# Saturn.net
KiCad netlist of a schematic drawn in EAGLE
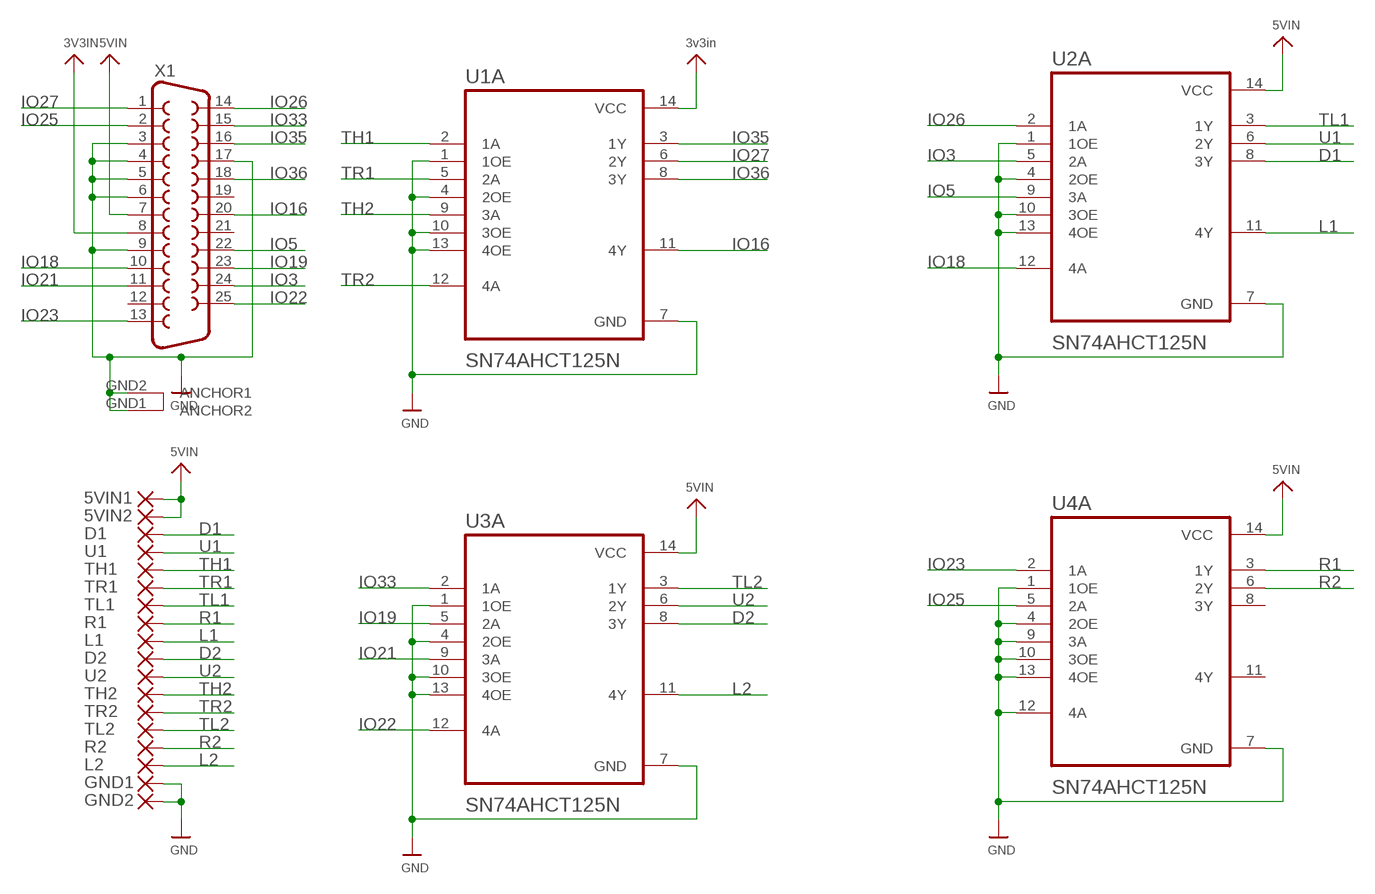
[diagram p0: schematic, sheet 1]

(export (version "E")
  (design (tool "Eeschema 10.0.6"))
  (components
    (comp (ref "5VIN1")
      (value "SMD5")
      (footprint "eagle-import:SMD2,54-5,08")
      (libsource (lib "eagle-import") (part "SMD5"))
    )
    (comp (ref "5VIN2")
      (value "SMD5")
      (footprint "eagle-import:SMD2,54-5,08")
      (libsource (lib "eagle-import") (part "SMD5"))
    )
    (comp (ref "D1")
      (value "SMD5")
      (footprint "eagle-import:SMD2,54-5,08")
      (libsource (lib "eagle-import") (part "SMD5"))
    )
    (comp (ref "D2")
      (value "SMD5")
      (footprint "eagle-import:SMD2,54-5,08")
      (libsource (lib "eagle-import") (part "SMD5"))
    )
    (comp (ref "GND1")
      (value "SMD5")
      (footprint "eagle-import:SMD2,54-5,08")
      (libsource (lib "eagle-import") (part "SMD5"))
    )
    (comp (ref "GND2")
      (value "SMD5")
      (footprint "eagle-import:SMD2,54-5,08")
      (libsource (lib "eagle-import") (part "SMD5"))
    )
    (comp (ref "L1")
      (value "SMD5")
      (footprint "eagle-import:SMD2,54-5,08")
      (libsource (lib "eagle-import") (part "SMD5"))
    )
    (comp (ref "L2")
      (value "SMD5")
      (footprint "eagle-import:SMD2,54-5,08")
      (libsource (lib "eagle-import") (part "SMD5"))
    )
    (comp (ref "R1")
      (value "SMD5")
      (footprint "eagle-import:SMD2,54-5,08")
      (libsource (lib "eagle-import") (part "SMD5"))
    )
    (comp (ref "R2")
      (value "SMD5")
      (footprint "eagle-import:SMD2,54-5,08")
      (libsource (lib "eagle-import") (part "SMD5"))
    )
    (comp (ref "TH1")
      (value "SMD5")
      (footprint "eagle-import:SMD2,54-5,08")
      (libsource (lib "eagle-import") (part "SMD5"))
    )
    (comp (ref "TH2")
      (value "SMD5")
      (footprint "eagle-import:SMD2,54-5,08")
      (libsource (lib "eagle-import") (part "SMD5"))
    )
    (comp (ref "TL1")
      (value "SMD5")
      (footprint "eagle-import:SMD2,54-5,08")
      (libsource (lib "eagle-import") (part "SMD5"))
    )
    (comp (ref "TL2")
      (value "SMD5")
      (footprint "eagle-import:SMD2,54-5,08")
      (libsource (lib "eagle-import") (part "SMD5"))
    )
    (comp (ref "TR1")
      (value "SMD5")
      (footprint "eagle-import:SMD2,54-5,08")
      (libsource (lib "eagle-import") (part "SMD5"))
    )
    (comp (ref "TR2")
      (value "SMD5")
      (footprint "eagle-import:SMD2,54-5,08")
      (libsource (lib "eagle-import") (part "SMD5"))
    )
    (comp (ref "U1")
      (value "SMD5")
      (footprint "eagle-import:SMD2,54-5,08")
      (libsource (lib "eagle-import") (part "SMD5"))
    )
    (comp (ref "U1A")
      (value "SN74AHCT125N")
      (footprint "eagle-import:DIP794W45P254L1969H508Q14")
      (fields (field (name "MF") "Texas Instruments"))
      (libsource (lib "eagle-import") (part "SN74AHCT125N"))
    )
    (comp (ref "U2")
      (value "SMD5")
      (footprint "eagle-import:SMD2,54-5,08")
      (libsource (lib "eagle-import") (part "SMD5"))
    )
    (comp (ref "U2A")
      (value "SN74AHCT125N")
      (footprint "eagle-import:DIP794W45P254L1969H508Q14")
      (fields (field (name "MF") "Texas Instruments"))
      (libsource (lib "eagle-import") (part "SN74AHCT125N"))
    )
    (comp (ref "U3A")
      (value "SN74AHCT125N")
      (footprint "eagle-import:DIP794W45P254L1969H508Q14")
      (fields (field (name "MF") "Texas Instruments"))
      (libsource (lib "eagle-import") (part "SN74AHCT125N"))
    )
    (comp (ref "U4A")
      (value "SN74AHCT125N")
      (footprint "eagle-import:DIP794W45P254L1969H508Q14")
      (fields (field (name "MF") "Texas Instruments"))
      (libsource (lib "eagle-import") (part "SN74AHCT125N"))
    )
    (comp (ref "X1")
      (value "DB25_FEMALEHP")
      (footprint "eagle-import:F25HP")
      (libsource (lib "eagle-import") (part "DB25_FEMALEHP"))
    )
  )
  (nets
    (net (code "1") (name "/D1") (class "Default")
      (node (ref "D1") (pin "1") (pinfunction "P_1") (pintype "passive"))
      (node (ref "U2A") (pin "8") (pinfunction "3Y_8") (pintype "output"))
    )
    (net (code "2") (name "/D2") (class "Default")
      (node (ref "D2") (pin "1") (pinfunction "P_1") (pintype "passive"))
      (node (ref "U3A") (pin "8") (pinfunction "3Y_8") (pintype "output"))
    )
    (net (code "3") (name "/IO3") (class "Default")
      (node (ref "U2A") (pin "5") (pinfunction "2A_5") (pintype "input"))
      (node (ref "X1") (pin "24") (pinfunction "24_24") (pintype "passive"))
    )
    (net (code "4") (name "/IO5") (class "Default")
      (node (ref "U2A") (pin "9") (pinfunction "3A_9") (pintype "input"))
      (node (ref "X1") (pin "22") (pinfunction "22_22") (pintype "passive"))
    )
    (net (code "5") (name "/IO16") (class "Default")
      (node (ref "U1A") (pin "11") (pinfunction "4Y_11") (pintype "output"))
      (node (ref "X1") (pin "20") (pinfunction "20_20") (pintype "passive"))
    )
    (net (code "6") (name "/IO18") (class "Default")
      (node (ref "U2A") (pin "12") (pinfunction "4A_12") (pintype "bidirectional"))
      (node (ref "X1") (pin "10") (pinfunction "10_10") (pintype "passive"))
    )
    (net (code "7") (name "/IO19") (class "Default")
      (node (ref "U3A") (pin "5") (pinfunction "2A_5") (pintype "input"))
      (node (ref "X1") (pin "23") (pinfunction "23_23") (pintype "passive"))
    )
    (net (code "8") (name "/IO21") (class "Default")
      (node (ref "U3A") (pin "9") (pinfunction "3A_9") (pintype "input"))
      (node (ref "X1") (pin "11") (pinfunction "11_11") (pintype "passive"))
    )
    (net (code "9") (name "/IO22") (class "Default")
      (node (ref "U3A") (pin "12") (pinfunction "4A_12") (pintype "bidirectional"))
      (node (ref "X1") (pin "25") (pinfunction "25_25") (pintype "passive"))
    )
    (net (code "10") (name "/IO23") (class "Default")
      (node (ref "U4A") (pin "2") (pinfunction "1A_2") (pintype "input"))
      (node (ref "X1") (pin "13") (pinfunction "13_13") (pintype "passive"))
    )
    (net (code "11") (name "/IO25") (class "Default")
      (node (ref "U4A") (pin "5") (pinfunction "2A_5") (pintype "input"))
      (node (ref "X1") (pin "2") (pinfunction "2_2") (pintype "passive"))
    )
    (net (code "12") (name "/IO26") (class "Default")
      (node (ref "U2A") (pin "2") (pinfunction "1A_2") (pintype "input"))
      (node (ref "X1") (pin "14") (pinfunction "14_14") (pintype "passive"))
    )
    (net (code "13") (name "/IO27") (class "Default")
      (node (ref "U1A") (pin "6") (pinfunction "2Y_6") (pintype "output"))
      (node (ref "X1") (pin "1") (pinfunction "1_1") (pintype "passive"))
    )
    (net (code "14") (name "/IO33") (class "Default")
      (node (ref "U3A") (pin "2") (pinfunction "1A_2") (pintype "input"))
      (node (ref "X1") (pin "15") (pinfunction "15_15") (pintype "passive"))
    )
    (net (code "15") (name "/IO35") (class "Default")
      (node (ref "U1A") (pin "3") (pinfunction "1Y_3") (pintype "output"))
      (node (ref "X1") (pin "16") (pinfunction "16_16") (pintype "passive"))
    )
    (net (code "16") (name "/IO36") (class "Default")
      (node (ref "U1A") (pin "8") (pinfunction "3Y_8") (pintype "output"))
      (node (ref "X1") (pin "18") (pinfunction "18_18") (pintype "passive"))
    )
    (net (code "17") (name "/L1") (class "Default")
      (node (ref "L1") (pin "1") (pinfunction "P_1") (pintype "passive"))
      (node (ref "U2A") (pin "11") (pinfunction "4Y_11") (pintype "output"))
    )
    (net (code "18") (name "/L2") (class "Default")
      (node (ref "L2") (pin "1") (pinfunction "P_1") (pintype "passive"))
      (node (ref "U3A") (pin "11") (pinfunction "4Y_11") (pintype "output"))
    )
    (net (code "19") (name "/R1") (class "Default")
      (node (ref "R1") (pin "1") (pinfunction "P_1") (pintype "passive"))
      (node (ref "U4A") (pin "3") (pinfunction "1Y_3") (pintype "output"))
    )
    (net (code "20") (name "/R2") (class "Default")
      (node (ref "R2") (pin "1") (pinfunction "P_1") (pintype "passive"))
      (node (ref "U4A") (pin "6") (pinfunction "2Y_6") (pintype "output"))
    )
    (net (code "21") (name "/TH1") (class "Default")
      (node (ref "TH1") (pin "1") (pinfunction "P_1") (pintype "passive"))
      (node (ref "U1A") (pin "2") (pinfunction "1A_2") (pintype "input"))
    )
    (net (code "22") (name "/TH2") (class "Default")
      (node (ref "TH2") (pin "1") (pinfunction "P_1") (pintype "passive"))
      (node (ref "U1A") (pin "9") (pinfunction "3A_9") (pintype "input"))
    )
    (net (code "23") (name "/TL1") (class "Default")
      (node (ref "TL1") (pin "1") (pinfunction "P_1") (pintype "passive"))
      (node (ref "U2A") (pin "3") (pinfunction "1Y_3") (pintype "output"))
    )
    (net (code "24") (name "/TL2") (class "Default")
      (node (ref "TL2") (pin "1") (pinfunction "P_1") (pintype "passive"))
      (node (ref "U3A") (pin "3") (pinfunction "1Y_3") (pintype "output"))
    )
    (net (code "25") (name "/TR1") (class "Default")
      (node (ref "TR1") (pin "1") (pinfunction "P_1") (pintype "passive"))
      (node (ref "U1A") (pin "5") (pinfunction "2A_5") (pintype "input"))
    )
    (net (code "26") (name "/TR2") (class "Default")
      (node (ref "TR2") (pin "1") (pinfunction "P_1") (pintype "passive"))
      (node (ref "U1A") (pin "12") (pinfunction "4A_12") (pintype "bidirectional"))
    )
    (net (code "27") (name "/U1") (class "Default")
      (node (ref "U1") (pin "1") (pinfunction "P_1") (pintype "passive"))
      (node (ref "U2A") (pin "6") (pinfunction "2Y_6") (pintype "output"))
    )
    (net (code "28") (name "/U2") (class "Default")
      (node (ref "U2") (pin "1") (pinfunction "P_1") (pintype "passive"))
      (node (ref "U3A") (pin "6") (pinfunction "2Y_6") (pintype "output"))
    )
    (net (code "29") (name "3V3IN") (class "Default")
      (node (ref "U1A") (pin "14") (pinfunction "VCC_14") (pintype "power_in"))
      (node (ref "X1") (pin "8") (pinfunction "8_8") (pintype "passive"))
    )
    (net (code "30") (name "5VIN") (class "Default")
      (node (ref "5VIN1") (pin "1") (pinfunction "P_1") (pintype "passive"))
      (node (ref "5VIN2") (pin "1") (pinfunction "P_1") (pintype "passive"))
      (node (ref "U2A") (pin "14") (pinfunction "VCC_14") (pintype "power_in"))
      (node (ref "U3A") (pin "14") (pinfunction "VCC_14") (pintype "power_in"))
      (node (ref "U4A") (pin "14") (pinfunction "VCC_14") (pintype "power_in"))
      (node (ref "X1") (pin "7") (pinfunction "7_7") (pintype "passive"))
    )
    (net (code "31") (name "GND") (class "Default")
      (node (ref "GND1") (pin "1") (pinfunction "P_1") (pintype "passive"))
      (node (ref "GND2") (pin "1") (pinfunction "P_1") (pintype "passive"))
      (node (ref "U1A") (pin "1") (pinfunction "1OE_1") (pintype "input"))
      (node (ref "U1A") (pin "10") (pinfunction "3OE_10") (pintype "input"))
      (node (ref "U1A") (pin "13") (pinfunction "4OE_13") (pintype "input"))
      (node (ref "U1A") (pin "4") (pinfunction "2OE_4") (pintype "input"))
      (node (ref "U1A") (pin "7") (pinfunction "GND_7") (pintype "power_in"))
      (node (ref "U2A") (pin "1") (pinfunction "1OE_1") (pintype "input"))
      (node (ref "U2A") (pin "10") (pinfunction "3OE_10") (pintype "input"))
      (node (ref "U2A") (pin "13") (pinfunction "4OE_13") (pintype "input"))
      (node (ref "U2A") (pin "4") (pinfunction "2OE_4") (pintype "input"))
      (node (ref "U2A") (pin "7") (pinfunction "GND_7") (pintype "power_in"))
      (node (ref "U3A") (pin "1") (pinfunction "1OE_1") (pintype "input"))
      (node (ref "U3A") (pin "10") (pinfunction "3OE_10") (pintype "input"))
      (node (ref "U3A") (pin "13") (pinfunction "4OE_13") (pintype "input"))
      (node (ref "U3A") (pin "4") (pinfunction "2OE_4") (pintype "input"))
      (node (ref "U3A") (pin "7") (pinfunction "GND_7") (pintype "power_in"))
      (node (ref "U4A") (pin "1") (pinfunction "1OE_1") (pintype "input"))
      (node (ref "U4A") (pin "10") (pinfunction "3OE_10") (pintype "input"))
      (node (ref "U4A") (pin "12") (pinfunction "4A_12") (pintype "bidirectional"))
      (node (ref "U4A") (pin "13") (pinfunction "4OE_13") (pintype "input"))
      (node (ref "U4A") (pin "4") (pinfunction "2OE_4") (pintype "input"))
      (node (ref "U4A") (pin "7") (pinfunction "GND_7") (pintype "power_in"))
      (node (ref "U4A") (pin "9") (pinfunction "3A_9") (pintype "input"))
      (node (ref "X1") (pin "17") (pinfunction "17_17") (pintype "passive"))
      (node (ref "X1") (pin "3") (pinfunction "3_3") (pintype "passive"))
      (node (ref "X1") (pin "4") (pinfunction "4_4") (pintype "passive"))
      (node (ref "X1") (pin "5") (pinfunction "5_5") (pintype "passive"))
      (node (ref "X1") (pin "6") (pinfunction "6_6") (pintype "passive"))
      (node (ref "X1") (pin "9") (pinfunction "9_9") (pintype "passive"))
      (node (ref "X1") (pin "GND1") (pinfunction "ANCHOR2_GND1") (pintype "bidirectional"))
      (node (ref "X1") (pin "GND2") (pinfunction "ANCHOR1_GND2") (pintype "bidirectional"))
    )
    (net (code "32") (name "unconnected-(U4A-3Y-Pad8)") (class "Default")
      (node (ref "U4A") (pin "8") (pinfunction "3Y_8") (pintype "output"))
    )
    (net (code "33") (name "unconnected-(U4A-4Y-Pad11)") (class "Default")
      (node (ref "U4A") (pin "11") (pinfunction "4Y_11") (pintype "output"))
    )
    (net (code "34") (name "unconnected-(X1-Pad12)") (class "Default")
      (node (ref "X1") (pin "12") (pinfunction "12_12") (pintype "passive"))
    )
    (net (code "35") (name "unconnected-(X1-Pad19)") (class "Default")
      (node (ref "X1") (pin "19") (pinfunction "19_19") (pintype "passive"))
    )
    (net (code "36") (name "unconnected-(X1-Pad21)") (class "Default")
      (node (ref "X1") (pin "21") (pinfunction "21_21") (pintype "passive"))
    )
  )
)
